# SCH_SmartHome-Breakout_2025-02-25.net
KiCad netlist of a schematic drawn in EasyEDA
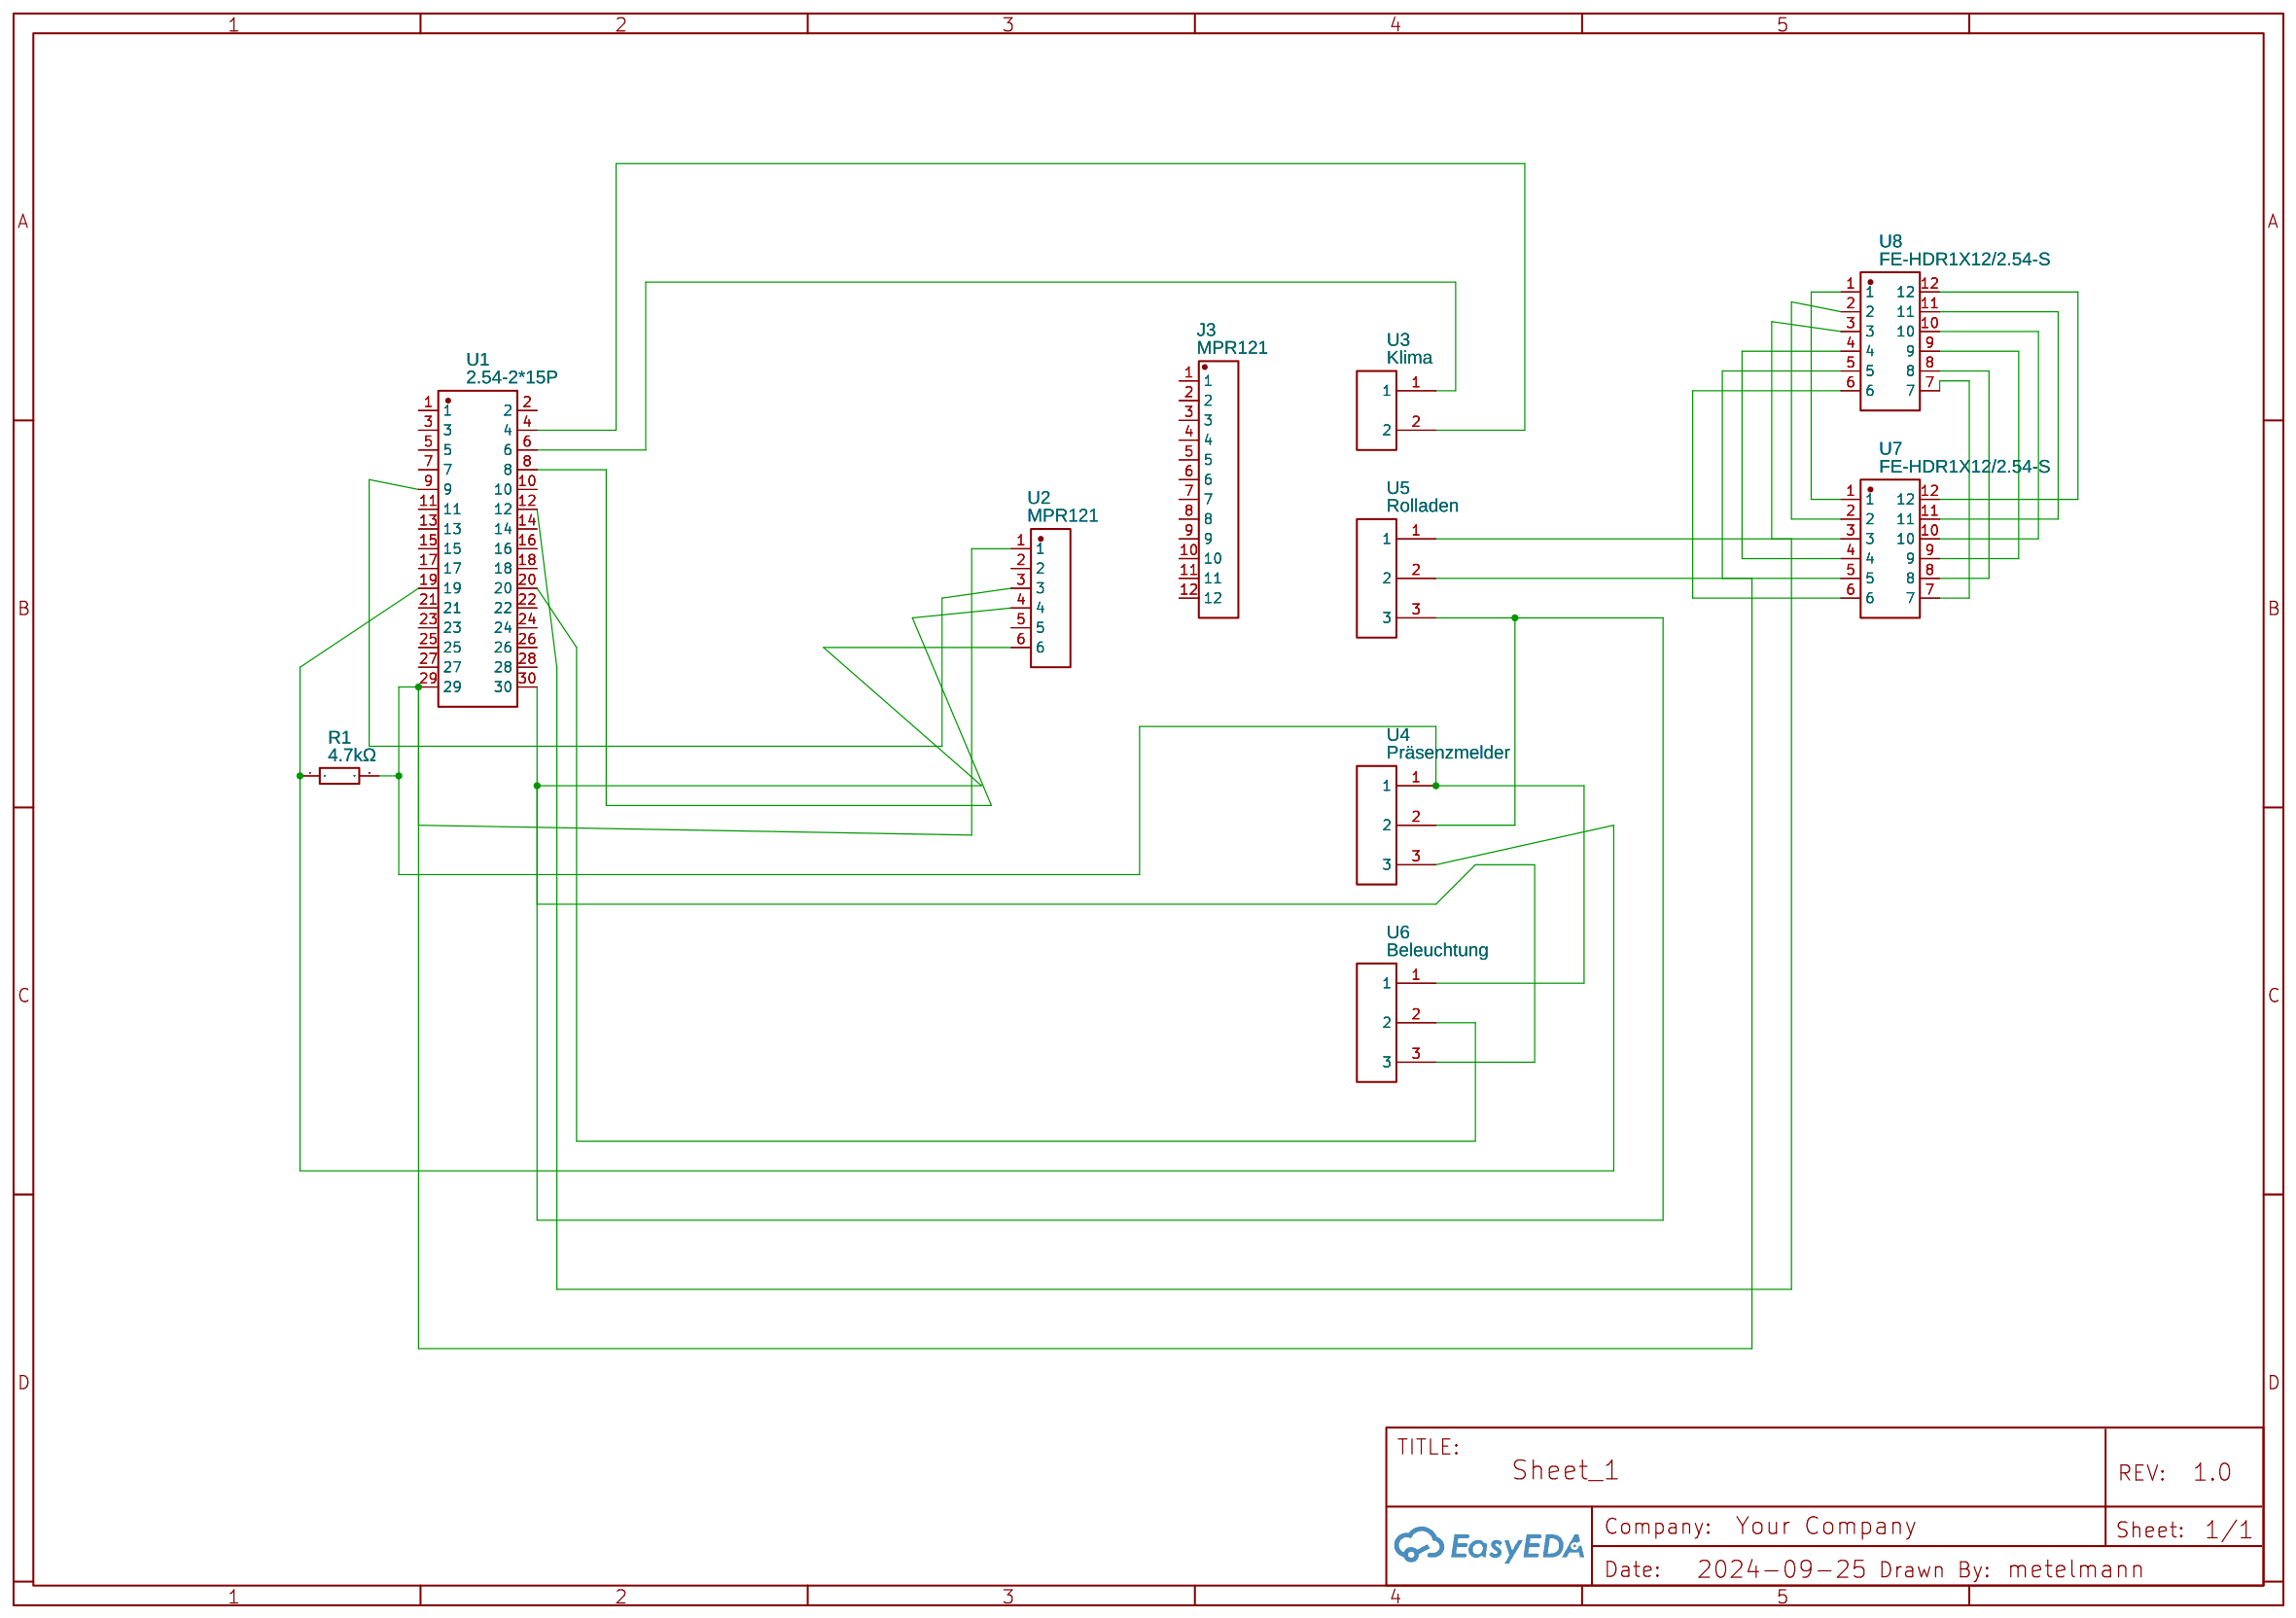
[diagram p0: schematic sheet]

(export (version "E")
  (design (tool "Eeschema 10.0.6"))
  (components
    (comp (ref "J3")
      (value "MPR121")
      (fields (field (name "Manufacturer Part") "HeadersPins1x12P2.54mm"))
      (libsource (lib "") (part "HeadersPins1x12P2.54mm"))
    )
    (comp (ref "R1")
      (value "4.7kΩ")
      (fields
        (field (name "Manufacturer Part") "MF1/4W-4.7KΩ±1% T")
        (field (name "Manufacturer") "CCO(千志电子)")
      )
      (libsource (lib "") (part "MF1/4W-4.7KΩ±1% T52 MINI"))
    )
    (comp (ref "U1")
      (value "2.54-2*15P")
      (fields (field (name "Manufacturer") "BOOMELE(博穆精密)"))
      (libsource (lib "") (part "2.54-2*15P"))
    )
    (comp (ref "U2")
      (value "MPR121")
      (fields (field (name "Manufacturer Part") "2.54-1*6") (field (name "Manufacturer") "ZHOURI(洲日)"))
      (libsource (lib "") (part "2.54-1*6"))
    )
    (comp (ref "U3") (value "Klima") (libsource (lib "") (part "2pin connector")))
    (comp (ref "U4") (value "Präsenzmelder") (libsource (lib "") (part "3pin connector")))
    (comp (ref "U5") (value "Rolladen") (libsource (lib "") (part "3pin connector")))
    (comp (ref "U6") (value "Beleuchtung") (libsource (lib "") (part "3pin connector")))
    (comp (ref "U7")
      (value "FE-HDR1X12/2.54-S")
      (fields (field (name "Manufacturer Part") "Fe-HDR1X12/2.54-S"))
      (libsource (lib "") (part "FE-HDR1X12/2.54-S"))
    )
    (comp (ref "U8")
      (value "FE-HDR1X12/2.54-S")
      (fields (field (name "Manufacturer Part") "Fe-HDR1X12/2.54-S"))
      (libsource (lib "") (part "FE-HDR1X12/2.54-S"))
    )
  )
  (nets
    (net (code "1") (name "Net-(R1-Pad1)") (class "Default")
      (node (ref "R1") (pin "1") (pinfunction "1_1") (pintype "unspecified"))
      (node (ref "U1") (pin "19") (pinfunction "19_19") (pintype "unspecified"))
      (node (ref "U4") (pin "3") (pinfunction "3_3") (pintype "unspecified"))
    )
    (net (code "2") (name "Net-(R1-Pad2)") (class "Default")
      (node (ref "R1") (pin "2") (pinfunction "2_2") (pintype "unspecified"))
      (node (ref "U1") (pin "29") (pinfunction "29_29") (pintype "unspecified"))
      (node (ref "U2") (pin "1") (pinfunction "1_1") (pintype "unspecified"))
      (node (ref "U4") (pin "1") (pinfunction "1_1") (pintype "unspecified"))
      (node (ref "U5") (pin "2") (pinfunction "2_2") (pintype "unspecified"))
      (node (ref "U6") (pin "1") (pinfunction "1_1") (pintype "unspecified"))
    )
    (net (code "3") (name "Net-(U1-Pad4)") (class "Default")
      (node (ref "U1") (pin "4") (pinfunction "4_4") (pintype "unspecified"))
      (node (ref "U3") (pin "2") (pinfunction "2_2") (pintype "unspecified"))
    )
    (net (code "4") (name "Net-(U1-Pad6)") (class "Default")
      (node (ref "U1") (pin "6") (pinfunction "6_6") (pintype "unspecified"))
      (node (ref "U3") (pin "1") (pinfunction "1_1") (pintype "unspecified"))
    )
    (net (code "5") (name "Net-(U1-Pad8)") (class "Default")
      (node (ref "U1") (pin "8") (pinfunction "8_8") (pintype "unspecified"))
      (node (ref "U2") (pin "4") (pinfunction "4_4") (pintype "unspecified"))
    )
    (net (code "6") (name "Net-(U1-Pad9)") (class "Default")
      (node (ref "U1") (pin "9") (pinfunction "9_9") (pintype "unspecified"))
      (node (ref "U2") (pin "3") (pinfunction "3_3") (pintype "unspecified"))
    )
    (net (code "7") (name "Net-(U1-Pad12)") (class "Default")
      (node (ref "U1") (pin "12") (pinfunction "12_12") (pintype "unspecified"))
      (node (ref "U5") (pin "1") (pinfunction "1_1") (pintype "unspecified"))
    )
    (net (code "8") (name "Net-(U1-Pad20)") (class "Default")
      (node (ref "U1") (pin "20") (pinfunction "20_20") (pintype "unspecified"))
      (node (ref "U6") (pin "2") (pinfunction "2_2") (pintype "unspecified"))
    )
    (net (code "9") (name "Net-(U1-Pad30)") (class "Default")
      (node (ref "U1") (pin "30") (pinfunction "30_30") (pintype "unspecified"))
      (node (ref "U2") (pin "6") (pinfunction "6_6") (pintype "unspecified"))
      (node (ref "U4") (pin "2") (pinfunction "2_2") (pintype "unspecified"))
      (node (ref "U5") (pin "3") (pinfunction "3_3") (pintype "unspecified"))
      (node (ref "U6") (pin "3") (pinfunction "3_3") (pintype "unspecified"))
    )
    (net (code "10") (name "Net-(U7-Pad1)") (class "Default")
      (node (ref "U7") (pin "1") (pinfunction "1_1") (pintype "unspecified"))
      (node (ref "U8") (pin "1") (pinfunction "1_1") (pintype "unspecified"))
    )
    (net (code "11") (name "Net-(U7-Pad2)") (class "Default")
      (node (ref "U7") (pin "2") (pinfunction "2_2") (pintype "unspecified"))
      (node (ref "U8") (pin "2") (pinfunction "2_2") (pintype "unspecified"))
    )
    (net (code "12") (name "Net-(U7-Pad3)") (class "Default")
      (node (ref "U7") (pin "3") (pinfunction "3_3") (pintype "unspecified"))
      (node (ref "U8") (pin "3") (pinfunction "3_3") (pintype "unspecified"))
    )
    (net (code "13") (name "Net-(U7-Pad4)") (class "Default")
      (node (ref "U7") (pin "4") (pinfunction "4_4") (pintype "unspecified"))
      (node (ref "U8") (pin "4") (pinfunction "4_4") (pintype "unspecified"))
    )
    (net (code "14") (name "Net-(U7-Pad5)") (class "Default")
      (node (ref "U7") (pin "5") (pinfunction "5_5") (pintype "unspecified"))
      (node (ref "U8") (pin "5") (pinfunction "5_5") (pintype "unspecified"))
    )
    (net (code "15") (name "Net-(U7-Pad6)") (class "Default")
      (node (ref "U7") (pin "6") (pinfunction "6_6") (pintype "unspecified"))
      (node (ref "U8") (pin "6") (pinfunction "6_6") (pintype "unspecified"))
    )
    (net (code "16") (name "Net-(U7-Pad7)") (class "Default")
      (node (ref "U7") (pin "7") (pinfunction "7_7") (pintype "unspecified"))
      (node (ref "U8") (pin "7") (pinfunction "7_7") (pintype "unspecified"))
    )
    (net (code "17") (name "Net-(U7-Pad8)") (class "Default")
      (node (ref "U7") (pin "8") (pinfunction "8_8") (pintype "unspecified"))
      (node (ref "U8") (pin "8") (pinfunction "8_8") (pintype "unspecified"))
    )
    (net (code "18") (name "Net-(U7-Pad9)") (class "Default")
      (node (ref "U7") (pin "9") (pinfunction "9_9") (pintype "unspecified"))
      (node (ref "U8") (pin "9") (pinfunction "9_9") (pintype "unspecified"))
    )
    (net (code "19") (name "Net-(U7-Pad10)") (class "Default")
      (node (ref "U7") (pin "10") (pinfunction "10_10") (pintype "unspecified"))
      (node (ref "U8") (pin "10") (pinfunction "10_10") (pintype "unspecified"))
    )
    (net (code "20") (name "Net-(U7-Pad11)") (class "Default")
      (node (ref "U7") (pin "11") (pinfunction "11_11") (pintype "unspecified"))
      (node (ref "U8") (pin "11") (pinfunction "11_11") (pintype "unspecified"))
    )
    (net (code "21") (name "Net-(U7-Pad12)") (class "Default")
      (node (ref "U7") (pin "12") (pinfunction "12_12") (pintype "unspecified"))
      (node (ref "U8") (pin "12") (pinfunction "12_12") (pintype "unspecified"))
    )
    (net (code "22") (name "unconnected-(J3-Pad1)") (class "Default")
      (node (ref "J3") (pin "1") (pinfunction "1_1") (pintype "unspecified"))
    )
    (net (code "23") (name "unconnected-(J3-Pad2)") (class "Default")
      (node (ref "J3") (pin "2") (pinfunction "2_2") (pintype "unspecified"))
    )
    (net (code "24") (name "unconnected-(J3-Pad3)") (class "Default")
      (node (ref "J3") (pin "3") (pinfunction "3_3") (pintype "unspecified"))
    )
    (net (code "25") (name "unconnected-(J3-Pad4)") (class "Default")
      (node (ref "J3") (pin "4") (pinfunction "4_4") (pintype "unspecified"))
    )
    (net (code "26") (name "unconnected-(J3-Pad5)") (class "Default")
      (node (ref "J3") (pin "5") (pinfunction "5_5") (pintype "unspecified"))
    )
    (net (code "27") (name "unconnected-(J3-Pad6)") (class "Default")
      (node (ref "J3") (pin "6") (pinfunction "6_6") (pintype "unspecified"))
    )
    (net (code "28") (name "unconnected-(J3-Pad7)") (class "Default")
      (node (ref "J3") (pin "7") (pinfunction "7_7") (pintype "unspecified"))
    )
    (net (code "29") (name "unconnected-(J3-Pad8)") (class "Default")
      (node (ref "J3") (pin "8") (pinfunction "8_8") (pintype "unspecified"))
    )
    (net (code "30") (name "unconnected-(J3-Pad9)") (class "Default")
      (node (ref "J3") (pin "9") (pinfunction "9_9") (pintype "unspecified"))
    )
    (net (code "31") (name "unconnected-(J3-Pad10)") (class "Default")
      (node (ref "J3") (pin "10") (pinfunction "10_10") (pintype "unspecified"))
    )
    (net (code "32") (name "unconnected-(J3-Pad11)") (class "Default")
      (node (ref "J3") (pin "11") (pinfunction "11_11") (pintype "unspecified"))
    )
    (net (code "33") (name "unconnected-(J3-Pad12)") (class "Default")
      (node (ref "J3") (pin "12") (pinfunction "12_12") (pintype "unspecified"))
    )
    (net (code "34") (name "unconnected-(U1-Pad1)") (class "Default")
      (node (ref "U1") (pin "1") (pinfunction "1_1") (pintype "unspecified"))
    )
    (net (code "35") (name "unconnected-(U1-Pad2)") (class "Default")
      (node (ref "U1") (pin "2") (pinfunction "2_2") (pintype "unspecified"))
    )
    (net (code "36") (name "unconnected-(U1-Pad3)") (class "Default")
      (node (ref "U1") (pin "3") (pinfunction "3_3") (pintype "unspecified"))
    )
    (net (code "37") (name "unconnected-(U1-Pad5)") (class "Default")
      (node (ref "U1") (pin "5") (pinfunction "5_5") (pintype "unspecified"))
    )
    (net (code "38") (name "unconnected-(U1-Pad7)") (class "Default")
      (node (ref "U1") (pin "7") (pinfunction "7_7") (pintype "unspecified"))
    )
    (net (code "39") (name "unconnected-(U1-Pad10)") (class "Default")
      (node (ref "U1") (pin "10") (pinfunction "10_10") (pintype "unspecified"))
    )
    (net (code "40") (name "unconnected-(U1-Pad11)") (class "Default")
      (node (ref "U1") (pin "11") (pinfunction "11_11") (pintype "unspecified"))
    )
    (net (code "41") (name "unconnected-(U1-Pad13)") (class "Default")
      (node (ref "U1") (pin "13") (pinfunction "13_13") (pintype "unspecified"))
    )
    (net (code "42") (name "unconnected-(U1-Pad14)") (class "Default")
      (node (ref "U1") (pin "14") (pinfunction "14_14") (pintype "unspecified"))
    )
    (net (code "43") (name "unconnected-(U1-Pad15)") (class "Default")
      (node (ref "U1") (pin "15") (pinfunction "15_15") (pintype "unspecified"))
    )
    (net (code "44") (name "unconnected-(U1-Pad16)") (class "Default")
      (node (ref "U1") (pin "16") (pinfunction "16_16") (pintype "unspecified"))
    )
    (net (code "45") (name "unconnected-(U1-Pad17)") (class "Default")
      (node (ref "U1") (pin "17") (pinfunction "17_17") (pintype "unspecified"))
    )
    (net (code "46") (name "unconnected-(U1-Pad18)") (class "Default")
      (node (ref "U1") (pin "18") (pinfunction "18_18") (pintype "unspecified"))
    )
    (net (code "47") (name "unconnected-(U1-Pad21)") (class "Default")
      (node (ref "U1") (pin "21") (pinfunction "21_21") (pintype "unspecified"))
    )
    (net (code "48") (name "unconnected-(U1-Pad22)") (class "Default")
      (node (ref "U1") (pin "22") (pinfunction "22_22") (pintype "unspecified"))
    )
    (net (code "49") (name "unconnected-(U1-Pad23)") (class "Default")
      (node (ref "U1") (pin "23") (pinfunction "23_23") (pintype "unspecified"))
    )
    (net (code "50") (name "unconnected-(U1-Pad24)") (class "Default")
      (node (ref "U1") (pin "24") (pinfunction "24_24") (pintype "unspecified"))
    )
    (net (code "51") (name "unconnected-(U1-Pad25)") (class "Default")
      (node (ref "U1") (pin "25") (pinfunction "25_25") (pintype "unspecified"))
    )
    (net (code "52") (name "unconnected-(U1-Pad26)") (class "Default")
      (node (ref "U1") (pin "26") (pinfunction "26_26") (pintype "unspecified"))
    )
    (net (code "53") (name "unconnected-(U1-Pad27)") (class "Default")
      (node (ref "U1") (pin "27") (pinfunction "27_27") (pintype "unspecified"))
    )
    (net (code "54") (name "unconnected-(U1-Pad28)") (class "Default")
      (node (ref "U1") (pin "28") (pinfunction "28_28") (pintype "unspecified"))
    )
    (net (code "55") (name "unconnected-(U2-Pad2)") (class "Default")
      (node (ref "U2") (pin "2") (pinfunction "2_2") (pintype "unspecified"))
    )
    (net (code "56") (name "unconnected-(U2-Pad5)") (class "Default")
      (node (ref "U2") (pin "5") (pinfunction "5_5") (pintype "unspecified"))
    )
  )
)
